# ET4207_DEBUG.net
KiCad netlist of a schematic drawn in Altium Designer
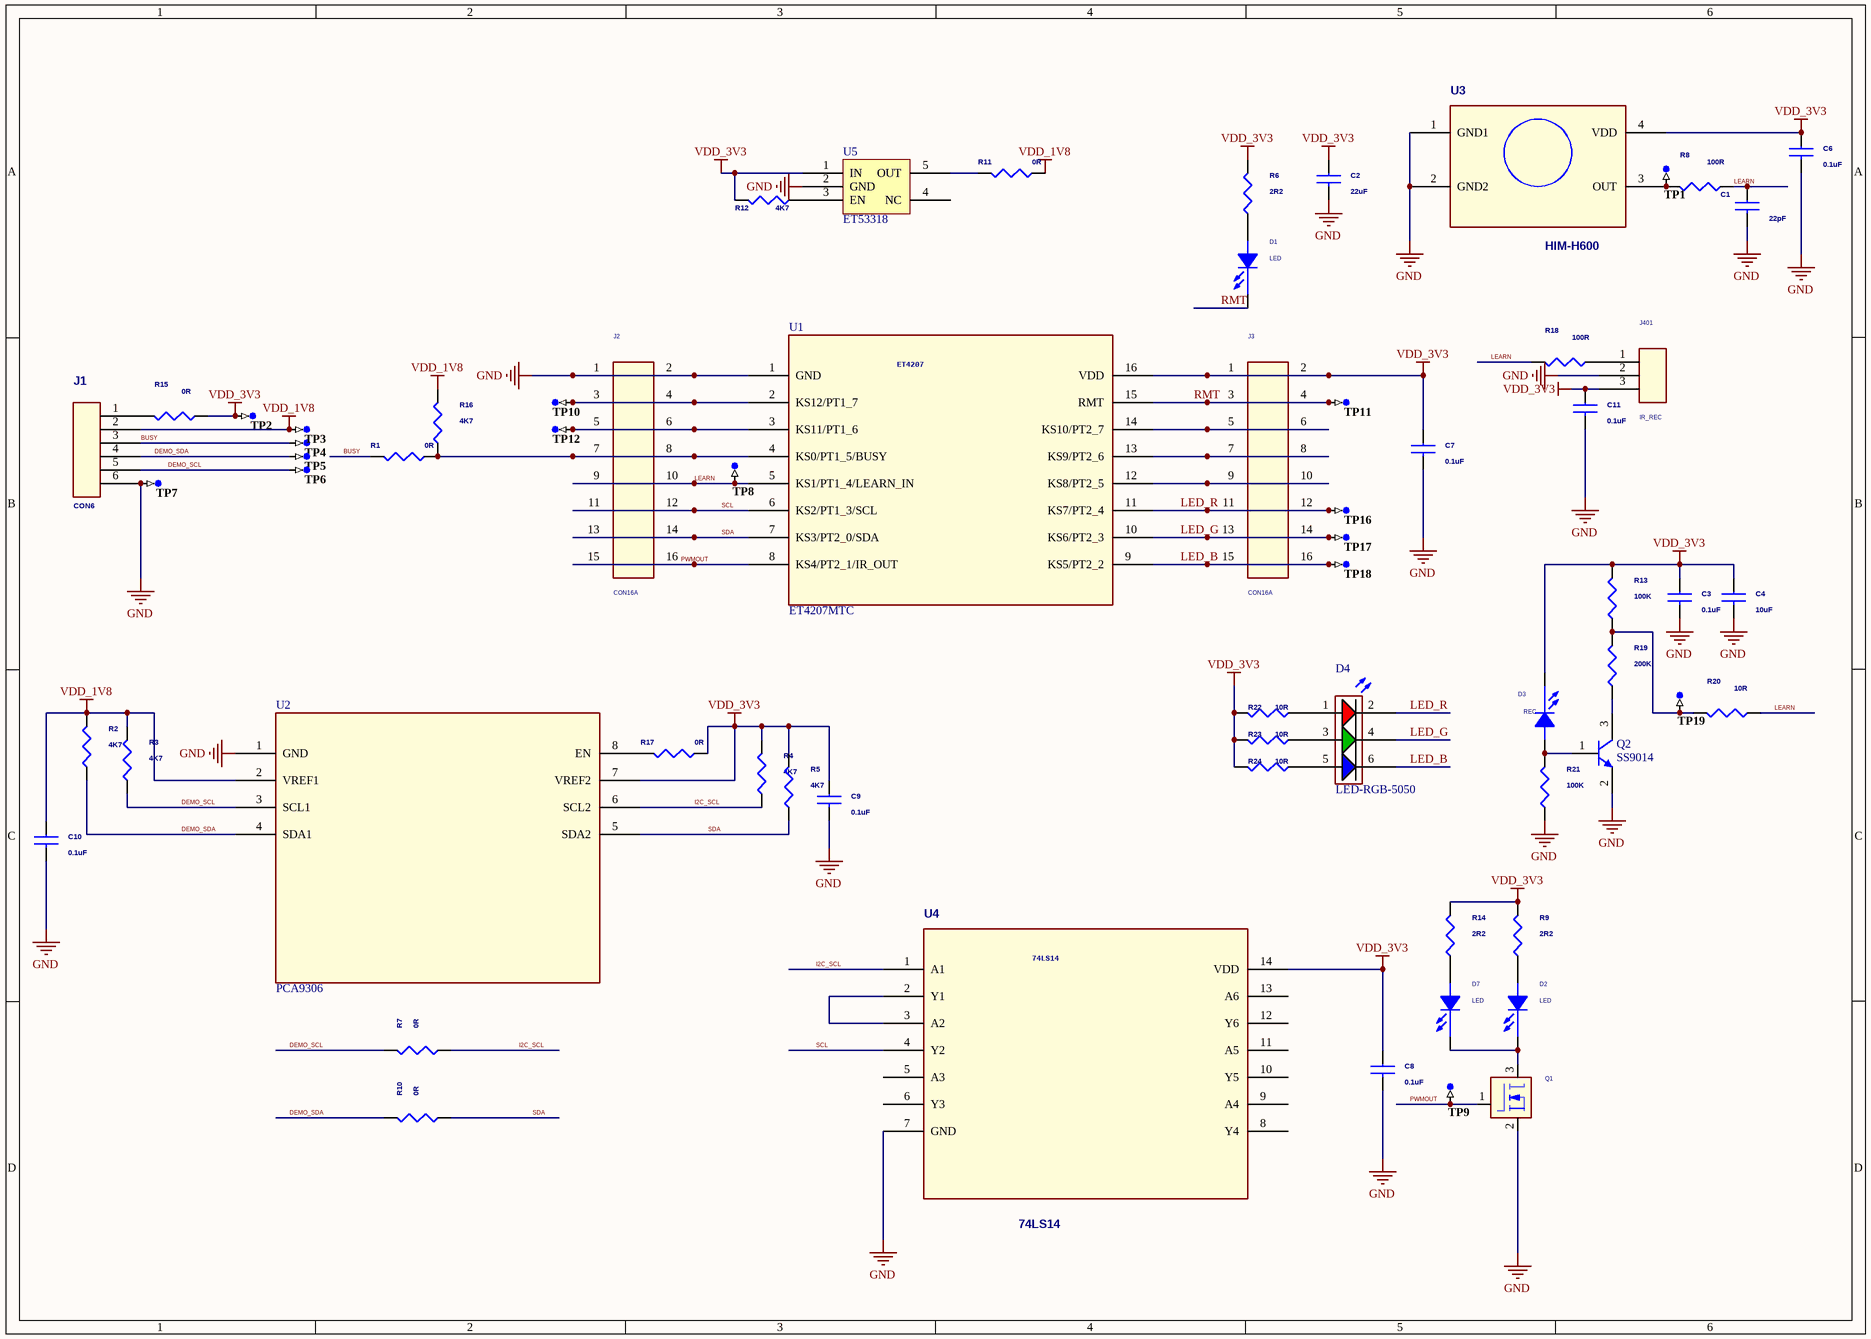
[diagram p0: ET4207_DEBUG.SchDoc]

(export (version "E")
  (design (tool "Eeschema 10.0.6"))
  (components
    (comp (ref "C1") (value "22pF") (footprint "0805C") (libsource (lib "*") (part "CAPACITOR NON-POL")))
    (comp (ref "C2") (value "22uF") (footprint "0805C") (libsource (lib "*") (part "CAPACITOR NON-POL")))
    (comp (ref "C3") (value "0.1uF") (footprint "0805C") (libsource (lib "*") (part "CAPACITOR NON-POL")))
    (comp (ref "C4") (value "10uF") (footprint "0805C") (libsource (lib "*") (part "CAPACITOR NON-POL")))
    (comp (ref "C6") (value "0.1uF") (footprint "0805C") (libsource (lib "*") (part "CAPACITOR NON-POL")))
    (comp (ref "C7") (value "0.1uF") (footprint "0805C") (libsource (lib "*") (part "CAPACITOR NON-POL")))
    (comp (ref "C8") (value "0.1uF") (footprint "0805C") (libsource (lib "*") (part "CAPACITOR NON-POL")))
    (comp (ref "C9") (value "0.1uF") (footprint "0805C") (libsource (lib "*") (part "CAPACITOR NON-POL")))
    (comp (ref "C10") (value "0.1uF") (footprint "0805C") (libsource (lib "*") (part "CAPACITOR NON-POL")))
    (comp (ref "C11") (value "0.1uF") (footprint "0805C") (libsource (lib "*") (part "CAPACITOR NON-POL")))
    (comp (ref "D1") (value "LED") (footprint "LED_A2") (libsource (lib "*") (part "LED_3")))
    (comp (ref "D2") (value "LED") (footprint "LED-0805") (libsource (lib "*") (part "LED_3")))
    (comp (ref "D3") (value "REC") (footprint "LED_A2") (libsource (lib "*") (part "LED_3")))
    (comp (ref "D4")
      (value "LED-RGB-5050")
      (footprint "LED-5050")
      (description "三基色LED")
      (fields (field (name "PUBLISHER") "Altium Limited"))
      (libsource (lib "sommer") (part "LED-RGB-5050"))
    )
    (comp (ref "D7") (value "LED") (footprint "LED_A2") (libsource (lib "*") (part "LED_3")))
    (comp (ref "J1") (value "CON6") (footprint "HDR1X6") (libsource (lib "*") (part "CON6")))
    (comp (ref "J2") (value "CON16A") (footprint "DIP16-2.54") (libsource (lib "*") (part "CON16A_0")))
    (comp (ref "J3") (value "CON16A") (footprint "DIP16-2.54") (libsource (lib "*") (part "CON16A_0")))
    (comp (ref "J401") (value "IR_REC") (footprint "IR") (libsource (lib "*") (part "CON3_0")))
    (comp (ref "Q1")
      (value "AO3400")
      (footprint "SOT-23")
      (description "MOSFET N-CH 50V 200MA SOT-23")
      (fields
        (field (name "TI_PART_NO") "TI-MOS-BSS138LT3G")
        (field (name "DISTRIBUTOR_PART_NUMBER") "BSS138LT3GOSCT-ND")
      )
      (libsource (lib "*") (part "MOSFET_I_EN_GSD"))
    )
    (comp (ref "Q2")
      (value "SS9014")
      (footprint "SOT23-3")
      (description "NPN贴片三极管")
      (fields (field (name "PUBLISHER") "Altium Limited"))
      (libsource (lib "sommer") (part "SS9014"))
    )
    (comp (ref "R1") (value "0R") (footprint "0805R") (libsource (lib "*") (part "RESISTOR")))
    (comp (ref "R2") (value "4K7") (footprint "0805R") (libsource (lib "*") (part "RESISTOR")))
    (comp (ref "R3") (value "4K7") (footprint "0805R") (libsource (lib "*") (part "RESISTOR")))
    (comp (ref "R4") (value "4K7") (footprint "0805R") (libsource (lib "*") (part "RESISTOR")))
    (comp (ref "R5") (value "4K7") (footprint "0805R") (libsource (lib "*") (part "RESISTOR")))
    (comp (ref "R6") (value "2R2") (footprint "0805R") (libsource (lib "*") (part "RESISTOR")))
    (comp (ref "R7") (value "0R") (footprint "0805R") (libsource (lib "*") (part "RESISTOR")))
    (comp (ref "R8") (value "100R") (footprint "0805R") (libsource (lib "*") (part "RESISTOR")))
    (comp (ref "R9") (value "2R2") (footprint "0805R") (libsource (lib "*") (part "RESISTOR")))
    (comp (ref "R10") (value "0R") (footprint "0805R") (libsource (lib "*") (part "RESISTOR")))
    (comp (ref "R11") (value "0R") (footprint "0805R") (libsource (lib "*") (part "RESISTOR")))
    (comp (ref "R12") (value "4K7") (footprint "0805R") (libsource (lib "*") (part "RESISTOR")))
    (comp (ref "R13") (value "100K") (footprint "0805R") (libsource (lib "*") (part "RESISTOR")))
    (comp (ref "R14") (value "2R2") (footprint "0805R") (libsource (lib "*") (part "RESISTOR")))
    (comp (ref "R15") (value "0R") (footprint "0805R") (libsource (lib "*") (part "RESISTOR")))
    (comp (ref "R16") (value "4K7") (footprint "0805R") (libsource (lib "*") (part "RESISTOR")))
    (comp (ref "R17") (value "0R") (footprint "0805R") (libsource (lib "*") (part "RESISTOR")))
    (comp (ref "R18") (value "100R") (footprint "0805R") (libsource (lib "*") (part "RESISTOR")))
    (comp (ref "R19") (value "200K") (footprint "0805R") (libsource (lib "*") (part "RESISTOR")))
    (comp (ref "R20") (value "10R") (footprint "0805R") (libsource (lib "*") (part "RESISTOR")))
    (comp (ref "R21") (value "100K") (footprint "0805R") (libsource (lib "*") (part "RESISTOR")))
    (comp (ref "R22") (value "10R") (footprint "0805R") (libsource (lib "*") (part "RESISTOR")))
    (comp (ref "R23") (value "10R") (footprint "0805R") (libsource (lib "*") (part "RESISTOR")))
    (comp (ref "R24") (value "10R") (footprint "0805R") (libsource (lib "*") (part "RESISTOR")))
    (comp (ref "TP1")
      (value "PULSE")
      (footprint "TP-SM-C-100")
      (description "Test Point, Surface Mount, Circular, Pad Diameter 1 mm")
      (libsource (lib "sommer") (part "TP-SM"))
    )
    (comp (ref "TP2")
      (value "3V3")
      (footprint "TP-SM-C-100")
      (description "Test Point, Surface Mount, Circular, Pad Diameter 1 mm")
      (libsource (lib "sommer") (part "TP-SM"))
    )
    (comp (ref "TP3")
      (value "1V8")
      (footprint "TP-SM-C-100")
      (description "Test Point, Surface Mount, Circular, Pad Diameter 1 mm")
      (libsource (lib "sommer") (part "TP-SM"))
    )
    (comp (ref "TP4")
      (value "BUSY")
      (footprint "TP-SM-C-100")
      (description "Test Point, Surface Mount, Circular, Pad Diameter 1 mm")
      (libsource (lib "sommer") (part "TP-SM"))
    )
    (comp (ref "TP5")
      (value "SDA")
      (footprint "TP-SM-C-100")
      (description "Test Point, Surface Mount, Circular, Pad Diameter 1 mm")
      (libsource (lib "sommer") (part "TP-SM"))
    )
    (comp (ref "TP6")
      (value "SCL")
      (footprint "TP-SM-C-100")
      (description "Test Point, Surface Mount, Circular, Pad Diameter 1 mm")
      (libsource (lib "sommer") (part "TP-SM"))
    )
    (comp (ref "TP7")
      (value "GND")
      (footprint "TP-SM-C-100")
      (description "Test Point, Surface Mount, Circular, Pad Diameter 1 mm")
      (libsource (lib "sommer") (part "TP-SM"))
    )
    (comp (ref "TP8")
      (value "LEARN")
      (footprint "TP-SM-C-100")
      (description "Test Point, Surface Mount, Circular, Pad Diameter 1 mm")
      (libsource (lib "sommer") (part "TP-SM"))
    )
    (comp (ref "TP9")
      (value "IROUT")
      (footprint "TP-SM-C-100")
      (description "Test Point, Surface Mount, Circular, Pad Diameter 1 mm")
      (libsource (lib "sommer") (part "TP-SM"))
    )
    (comp (ref "TP10")
      (value "PT17")
      (footprint "TP-SM-C-100")
      (description "Test Point, Surface Mount, Circular, Pad Diameter 1 mm")
      (libsource (lib "sommer") (part "TP-SM"))
    )
    (comp (ref "TP11")
      (value "SCL")
      (footprint "TP-SM-C-100")
      (description "Test Point, Surface Mount, Circular, Pad Diameter 1 mm")
      (libsource (lib "sommer") (part "TP-SM"))
    )
    (comp (ref "TP12")
      (value "PT16")
      (footprint "TP-SM-C-100")
      (description "Test Point, Surface Mount, Circular, Pad Diameter 1 mm")
      (libsource (lib "sommer") (part "TP-SM"))
    )
    (comp (ref "TP16")
      (value "PT24")
      (footprint "TP-SM-C-100")
      (description "Test Point, Surface Mount, Circular, Pad Diameter 1 mm")
      (libsource (lib "sommer") (part "TP-SM"))
    )
    (comp (ref "TP17")
      (value "PT23")
      (footprint "TP-SM-C-100")
      (description "Test Point, Surface Mount, Circular, Pad Diameter 1 mm")
      (libsource (lib "sommer") (part "TP-SM"))
    )
    (comp (ref "TP18")
      (value "PT22")
      (footprint "TP-SM-C-100")
      (description "Test Point, Surface Mount, Circular, Pad Diameter 1 mm")
      (libsource (lib "sommer") (part "TP-SM"))
    )
    (comp (ref "TP19")
      (value "DIODE_V")
      (footprint "TP-SM-C-100")
      (description "Test Point, Surface Mount, Circular, Pad Diameter 1 mm")
      (libsource (lib "sommer") (part "TP-SM"))
    )
    (comp (ref "U1")
      (value "ET4207MTC")
      (footprint "sommer:soic-16")
      (libsource (lib "ET4207_DEBUG_Library") (part "ET4207MTC"))
    )
    (comp (ref "U2")
      (value "PCA9306")
      (footprint "DCT-G8")
      (libsource (lib "ET4207_DEBUG_Library") (part "PCA9306"))
    )
    (comp (ref "U3") (value "HIM-H600") (footprint "HIM-H600") (libsource (lib "*") (part "LPC111x_7")))
    (comp (ref "U4")
      (value "74LS14")
      (footprint "sommer:SOIC-14")
      (libsource (lib "*") (part "STM32F103C8_1"))
    )
    (comp (ref "U5") (value "ET53318") (footprint "SOT23-5") (libsource (lib "sommer") (part "ET53333")))
  )
  (nets
    (net (code "1") (name "/BUSY") (class "Default")
      (node (ref "J1") (pin "3") (pinfunction "3_3") (pintype "passive"))
      (node (ref "R1") (pin "2") (pinfunction "2_2") (pintype "passive"))
      (node (ref "TP4") (pin "1") (pinfunction "1_1") (pintype "input"))
    )
    (net (code "2") (name "/DEMO_SCL") (class "Default")
      (node (ref "J1") (pin "5") (pinfunction "5_5") (pintype "passive"))
      (node (ref "R3") (pin "1") (pinfunction "1_1") (pintype "passive"))
      (node (ref "R7") (pin "2") (pinfunction "2_2") (pintype "passive"))
      (node (ref "TP6") (pin "1") (pinfunction "1_1") (pintype "input"))
      (node (ref "U2") (pin "3") (pinfunction "SCL1_3") (pintype "passive"))
    )
    (net (code "3") (name "/DEMO_SDA") (class "Default")
      (node (ref "J1") (pin "4") (pinfunction "4_4") (pintype "passive"))
      (node (ref "R10") (pin "2") (pinfunction "2_2") (pintype "passive"))
      (node (ref "R2") (pin "1") (pinfunction "1_1") (pintype "passive"))
      (node (ref "TP5") (pin "1") (pinfunction "1_1") (pintype "input"))
      (node (ref "U2") (pin "4") (pinfunction "SDA1_4") (pintype "passive"))
    )
    (net (code "4") (name "/I2C_SCL") (class "Default")
      (node (ref "R4") (pin "1") (pinfunction "1_1") (pintype "passive"))
      (node (ref "R7") (pin "1") (pinfunction "1_1") (pintype "passive"))
      (node (ref "U2") (pin "6") (pinfunction "SCL2_6") (pintype "passive"))
      (node (ref "U4") (pin "1") (pinfunction "A1_1") (pintype "passive"))
    )
    (net (code "5") (name "/LEARN") (class "Default")
      (node (ref "C1") (pin "1") (pinfunction "1_1") (pintype "passive"))
      (node (ref "J2") (pin "10") (pinfunction "10_10") (pintype "passive"))
      (node (ref "J2") (pin "9") (pinfunction "9_9") (pintype "passive"))
      (node (ref "R18") (pin "2") (pinfunction "2_2") (pintype "passive"))
      (node (ref "R20") (pin "1") (pinfunction "1_1") (pintype "passive"))
      (node (ref "R8") (pin "1") (pinfunction "1_1") (pintype "passive"))
      (node (ref "TP8") (pin "1") (pinfunction "1_1") (pintype "input"))
      (node (ref "U1") (pin "5") (pinfunction "KS1/PT1_4/LEARN_IN_5") (pintype "passive"))
    )
    (net (code "6") (name "/LED_B") (class "Default")
      (node (ref "D4") (pin "6") (pinfunction "B_6") (pintype "passive"))
      (node (ref "J3") (pin "15") (pinfunction "15_15") (pintype "passive"))
      (node (ref "J3") (pin "16") (pinfunction "16_16") (pintype "passive"))
      (node (ref "TP18") (pin "1") (pinfunction "1_1") (pintype "input"))
      (node (ref "U1") (pin "9") (pinfunction "KS5/PT2_2_9") (pintype "passive"))
    )
    (net (code "7") (name "/LED_G") (class "Default")
      (node (ref "D4") (pin "4") (pinfunction "G_4") (pintype "passive"))
      (node (ref "J3") (pin "13") (pinfunction "13_13") (pintype "passive"))
      (node (ref "J3") (pin "14") (pinfunction "14_14") (pintype "passive"))
      (node (ref "TP17") (pin "1") (pinfunction "1_1") (pintype "input"))
      (node (ref "U1") (pin "10") (pinfunction "KS6/PT2_3_10") (pintype "passive"))
    )
    (net (code "8") (name "/LED_R") (class "Default")
      (node (ref "D4") (pin "2") (pinfunction "R_2") (pintype "passive"))
      (node (ref "J3") (pin "11") (pinfunction "11_11") (pintype "passive"))
      (node (ref "J3") (pin "12") (pinfunction "12_12") (pintype "passive"))
      (node (ref "TP16") (pin "1") (pinfunction "1_1") (pintype "input"))
      (node (ref "U1") (pin "11") (pinfunction "KS7/PT2_4_11") (pintype "passive"))
    )
    (net (code "9") (name "/PWMOUT") (class "Default")
      (node (ref "J2") (pin "15") (pinfunction "15_15") (pintype "passive"))
      (node (ref "J2") (pin "16") (pinfunction "16_16") (pintype "passive"))
      (node (ref "Q1") (pin "1") (pinfunction "G_1") (pintype "passive"))
      (node (ref "TP9") (pin "1") (pinfunction "1_1") (pintype "input"))
      (node (ref "U1") (pin "8") (pinfunction "KS4/PT2_1/IR_OUT_8") (pintype "passive"))
    )
    (net (code "10") (name "/RMT") (class "Default")
      (node (ref "D1") (pin "2") (pinfunction "CATHODE_2") (pintype "passive"))
      (node (ref "J3") (pin "3") (pinfunction "3_3") (pintype "passive"))
      (node (ref "J3") (pin "4") (pinfunction "4_4") (pintype "passive"))
      (node (ref "TP11") (pin "1") (pinfunction "1_1") (pintype "input"))
      (node (ref "U1") (pin "15") (pinfunction "RMT_15") (pintype "passive"))
    )
    (net (code "11") (name "/SCL") (class "Default")
      (node (ref "J2") (pin "11") (pinfunction "11_11") (pintype "passive"))
      (node (ref "J2") (pin "12") (pinfunction "12_12") (pintype "passive"))
      (node (ref "U1") (pin "6") (pinfunction "KS2/PT1_3/SCL_6") (pintype "passive"))
      (node (ref "U4") (pin "4") (pinfunction "Y2_4") (pintype "passive"))
    )
    (net (code "12") (name "/SDA") (class "Default")
      (node (ref "J2") (pin "13") (pinfunction "13_13") (pintype "passive"))
      (node (ref "J2") (pin "14") (pinfunction "14_14") (pintype "passive"))
      (node (ref "R10") (pin "1") (pinfunction "1_1") (pintype "passive"))
      (node (ref "R5") (pin "1") (pinfunction "1_1") (pintype "passive"))
      (node (ref "U1") (pin "7") (pinfunction "KS3/PT2_0/SDA_7") (pintype "passive"))
      (node (ref "U2") (pin "5") (pinfunction "SDA2_5") (pintype "passive"))
    )
    (net (code "13") (name "GND") (class "Default")
      (node (ref "C1") (pin "2") (pinfunction "2_2") (pintype "passive"))
      (node (ref "C10") (pin "2") (pinfunction "2_2") (pintype "passive"))
      (node (ref "C11") (pin "2") (pinfunction "2_2") (pintype "passive"))
      (node (ref "C2") (pin "2") (pinfunction "2_2") (pintype "passive"))
      (node (ref "C3") (pin "2") (pinfunction "2_2") (pintype "passive"))
      (node (ref "C4") (pin "2") (pinfunction "2_2") (pintype "passive"))
      (node (ref "C6") (pin "2") (pinfunction "2_2") (pintype "passive"))
      (node (ref "C7") (pin "2") (pinfunction "2_2") (pintype "passive"))
      (node (ref "C8") (pin "2") (pinfunction "2_2") (pintype "passive"))
      (node (ref "C9") (pin "2") (pinfunction "2_2") (pintype "passive"))
      (node (ref "J1") (pin "6") (pinfunction "6_6") (pintype "passive"))
      (node (ref "J2") (pin "1") (pinfunction "1_1") (pintype "passive"))
      (node (ref "J2") (pin "2") (pinfunction "2_2") (pintype "passive"))
      (node (ref "J401") (pin "2") (pinfunction "GND_2") (pintype "passive"))
      (node (ref "Q1") (pin "2") (pinfunction "S_2") (pintype "passive"))
      (node (ref "Q2") (pin "2") (pinfunction "E_2") (pintype "passive"))
      (node (ref "R21") (pin "1") (pinfunction "1_1") (pintype "passive"))
      (node (ref "TP7") (pin "1") (pinfunction "1_1") (pintype "input"))
      (node (ref "U1") (pin "1") (pinfunction "GND_1") (pintype "passive"))
      (node (ref "U2") (pin "1") (pinfunction "GND_1") (pintype "passive"))
      (node (ref "U3") (pin "1") (pinfunction "GND1_1") (pintype "passive"))
      (node (ref "U3") (pin "2") (pinfunction "GND2_2") (pintype "passive"))
      (node (ref "U4") (pin "7") (pinfunction "GND_7") (pintype "passive"))
      (node (ref "U5") (pin "2") (pinfunction "GND_2") (pintype "passive"))
    )
    (net (code "14") (name "Net-(D1-ANODE)") (class "Default")
      (node (ref "D1") (pin "1") (pinfunction "ANODE_1") (pintype "passive"))
      (node (ref "R6") (pin "1") (pinfunction "1_1") (pintype "passive"))
    )
    (net (code "15") (name "Net-(D2-ANODE)") (class "Default")
      (node (ref "D2") (pin "1") (pinfunction "ANODE_1") (pintype "passive"))
      (node (ref "R9") (pin "1") (pinfunction "1_1") (pintype "passive"))
    )
    (net (code "16") (name "Net-(D2-CATHODE)") (class "Default")
      (node (ref "D2") (pin "2") (pinfunction "CATHODE_2") (pintype "passive"))
      (node (ref "D7") (pin "2") (pinfunction "CATHODE_2") (pintype "passive"))
      (node (ref "Q1") (pin "3") (pinfunction "D_3") (pintype "passive"))
    )
    (net (code "17") (name "Net-(D3-ANODE)") (class "Default")
      (node (ref "D3") (pin "1") (pinfunction "ANODE_1") (pintype "passive"))
      (node (ref "Q2") (pin "1") (pinfunction "B_1") (pintype "passive"))
      (node (ref "R21") (pin "2") (pinfunction "2_2") (pintype "passive"))
    )
    (net (code "18") (name "Net-(D4-A)") (class "Default")
      (node (ref "D4") (pin "3") (pinfunction "A_3") (pintype "passive"))
      (node (ref "R23") (pin "1") (pinfunction "1_1") (pintype "passive"))
    )
    (net (code "19") (name "Net-(D4-R-Pad1)") (class "Default")
      (node (ref "D4") (pin "1") (pinfunction "R_1") (pintype "passive"))
      (node (ref "R22") (pin "1") (pinfunction "1_1") (pintype "passive"))
    )
    (net (code "20") (name "Net-(D4-R-Pad5)") (class "Default")
      (node (ref "D4") (pin "5") (pinfunction "R_5") (pintype "passive"))
      (node (ref "R24") (pin "1") (pinfunction "1_1") (pintype "passive"))
    )
    (net (code "21") (name "Net-(D7-ANODE)") (class "Default")
      (node (ref "D7") (pin "1") (pinfunction "ANODE_1") (pintype "passive"))
      (node (ref "R14") (pin "1") (pinfunction "1_1") (pintype "passive"))
    )
    (net (code "22") (name "Net-(J1-Pad1)") (class "Default")
      (node (ref "J1") (pin "1") (pinfunction "1_1") (pintype "passive"))
      (node (ref "R15") (pin "2") (pinfunction "2_2") (pintype "passive"))
    )
    (net (code "23") (name "Net-(J401-IROUT)") (class "Default")
      (node (ref "J401") (pin "1") (pinfunction "IROUT_1") (pintype "passive"))
      (node (ref "R18") (pin "1") (pinfunction "1_1") (pintype "passive"))
    )
    (net (code "24") (name "Net-(Q2-C)") (class "Default")
      (node (ref "Q2") (pin "3") (pinfunction "C_3") (pintype "passive"))
      (node (ref "R19") (pin "1") (pinfunction "1_1") (pintype "passive"))
    )
    (net (code "25") (name "Net-(R13-Pad1)") (class "Default")
      (node (ref "R13") (pin "1") (pinfunction "1_1") (pintype "passive"))
      (node (ref "R19") (pin "2") (pinfunction "2_2") (pintype "passive"))
      (node (ref "R20") (pin "2") (pinfunction "2_2") (pintype "passive"))
      (node (ref "TP19") (pin "1") (pinfunction "1_1") (pintype "input"))
    )
    (net (code "26") (name "Net-(U1-KS0{slash}PT1_5{slash}BUSY)") (class "Default")
      (node (ref "J2") (pin "7") (pinfunction "7_7") (pintype "passive"))
      (node (ref "J2") (pin "8") (pinfunction "8_8") (pintype "passive"))
      (node (ref "R1") (pin "1") (pinfunction "1_1") (pintype "passive"))
      (node (ref "R16") (pin "1") (pinfunction "1_1") (pintype "passive"))
      (node (ref "U1") (pin "4") (pinfunction "KS0/PT1_5/BUSY_4") (pintype "passive"))
    )
    (net (code "27") (name "Net-(U1-KS8{slash}PT2_5)") (class "Default")
      (node (ref "J3") (pin "10") (pinfunction "10_10") (pintype "passive"))
      (node (ref "J3") (pin "9") (pinfunction "9_9") (pintype "passive"))
      (node (ref "U1") (pin "12") (pinfunction "KS8/PT2_5_12") (pintype "passive"))
    )
    (net (code "28") (name "Net-(U1-KS9{slash}PT2_6)") (class "Default")
      (node (ref "J3") (pin "7") (pinfunction "7_7") (pintype "passive"))
      (node (ref "J3") (pin "8") (pinfunction "8_8") (pintype "passive"))
      (node (ref "U1") (pin "13") (pinfunction "KS9/PT2_6_13") (pintype "passive"))
    )
    (net (code "29") (name "Net-(U1-KS10{slash}PT2_7)") (class "Default")
      (node (ref "J3") (pin "5") (pinfunction "5_5") (pintype "passive"))
      (node (ref "J3") (pin "6") (pinfunction "6_6") (pintype "passive"))
      (node (ref "U1") (pin "14") (pinfunction "KS10/PT2_7_14") (pintype "passive"))
    )
    (net (code "30") (name "Net-(U1-KS11{slash}PT1_6)") (class "Default")
      (node (ref "J2") (pin "5") (pinfunction "5_5") (pintype "passive"))
      (node (ref "J2") (pin "6") (pinfunction "6_6") (pintype "passive"))
      (node (ref "TP12") (pin "1") (pinfunction "1_1") (pintype "input"))
      (node (ref "U1") (pin "3") (pinfunction "KS11/PT1_6_3") (pintype "passive"))
    )
    (net (code "31") (name "Net-(U1-KS12{slash}PT1_7)") (class "Default")
      (node (ref "J2") (pin "3") (pinfunction "3_3") (pintype "passive"))
      (node (ref "J2") (pin "4") (pinfunction "4_4") (pintype "passive"))
      (node (ref "TP10") (pin "1") (pinfunction "1_1") (pintype "input"))
      (node (ref "U1") (pin "2") (pinfunction "KS12/PT1_7_2") (pintype "passive"))
    )
    (net (code "32") (name "Net-(U2-EN)") (class "Default")
      (node (ref "R17") (pin "2") (pinfunction "2_2") (pintype "passive"))
      (node (ref "U2") (pin "8") (pinfunction "EN_8") (pintype "passive"))
    )
    (net (code "33") (name "Net-(U3-OUT)") (class "Default")
      (node (ref "R8") (pin "2") (pinfunction "2_2") (pintype "passive"))
      (node (ref "TP1") (pin "1") (pinfunction "1_1") (pintype "input"))
      (node (ref "U3") (pin "3") (pinfunction "OUT_3") (pintype "passive"))
    )
    (net (code "34") (name "Net-(U4-A2)") (class "Default")
      (node (ref "U4") (pin "2") (pinfunction "Y1_2") (pintype "passive"))
      (node (ref "U4") (pin "3") (pinfunction "A2_3") (pintype "passive"))
    )
    (net (code "35") (name "Net-(U5-EN)") (class "Default")
      (node (ref "R12") (pin "1") (pinfunction "1_1") (pintype "passive"))
      (node (ref "U5") (pin "3") (pinfunction "EN_3") (pintype "passive"))
    )
    (net (code "36") (name "Net-(U5-OUT)") (class "Default")
      (node (ref "R11") (pin "2") (pinfunction "2_2") (pintype "passive"))
      (node (ref "U5") (pin "5") (pinfunction "OUT_5") (pintype "passive"))
    )
    (net (code "37") (name "VDD_1V8") (class "Default")
      (node (ref "C10") (pin "1") (pinfunction "1_1") (pintype "passive"))
      (node (ref "J1") (pin "2") (pinfunction "2_2") (pintype "passive"))
      (node (ref "R11") (pin "1") (pinfunction "1_1") (pintype "passive"))
      (node (ref "R16") (pin "2") (pinfunction "2_2") (pintype "passive"))
      (node (ref "R2") (pin "2") (pinfunction "2_2") (pintype "passive"))
      (node (ref "R3") (pin "2") (pinfunction "2_2") (pintype "passive"))
      (node (ref "TP3") (pin "1") (pinfunction "1_1") (pintype "input"))
      (node (ref "U2") (pin "2") (pinfunction "VREF1_2") (pintype "passive"))
    )
    (net (code "38") (name "VDD_3V3") (class "Default")
      (node (ref "C11") (pin "1") (pinfunction "1_1") (pintype "passive"))
      (node (ref "C2") (pin "1") (pinfunction "1_1") (pintype "passive"))
      (node (ref "C3") (pin "1") (pinfunction "1_1") (pintype "passive"))
      (node (ref "C4") (pin "1") (pinfunction "1_1") (pintype "passive"))
      (node (ref "C6") (pin "1") (pinfunction "1_1") (pintype "passive"))
      (node (ref "C7") (pin "1") (pinfunction "1_1") (pintype "passive"))
      (node (ref "C8") (pin "1") (pinfunction "1_1") (pintype "passive"))
      (node (ref "C9") (pin "1") (pinfunction "1_1") (pintype "passive"))
      (node (ref "D3") (pin "2") (pinfunction "CATHODE_2") (pintype "passive"))
      (node (ref "J3") (pin "1") (pinfunction "1_1") (pintype "passive"))
      (node (ref "J3") (pin "2") (pinfunction "2_2") (pintype "passive"))
      (node (ref "J401") (pin "3") (pinfunction "VCC_3") (pintype "passive"))
      (node (ref "R12") (pin "2") (pinfunction "2_2") (pintype "passive"))
      (node (ref "R13") (pin "2") (pinfunction "2_2") (pintype "passive"))
      (node (ref "R14") (pin "2") (pinfunction "2_2") (pintype "passive"))
      (node (ref "R15") (pin "1") (pinfunction "1_1") (pintype "passive"))
      (node (ref "R17") (pin "1") (pinfunction "1_1") (pintype "passive"))
      (node (ref "R22") (pin "2") (pinfunction "2_2") (pintype "passive"))
      (node (ref "R23") (pin "2") (pinfunction "2_2") (pintype "passive"))
      (node (ref "R24") (pin "2") (pinfunction "2_2") (pintype "passive"))
      (node (ref "R4") (pin "2") (pinfunction "2_2") (pintype "passive"))
      (node (ref "R5") (pin "2") (pinfunction "2_2") (pintype "passive"))
      (node (ref "R6") (pin "2") (pinfunction "2_2") (pintype "passive"))
      (node (ref "R9") (pin "2") (pinfunction "2_2") (pintype "passive"))
      (node (ref "TP2") (pin "1") (pinfunction "1_1") (pintype "input"))
      (node (ref "U1") (pin "16") (pinfunction "VDD_16") (pintype "passive"))
      (node (ref "U2") (pin "7") (pinfunction "VREF2_7") (pintype "passive"))
      (node (ref "U3") (pin "4") (pinfunction "VDD_4") (pintype "passive"))
      (node (ref "U4") (pin "14") (pinfunction "VDD_14") (pintype "passive"))
      (node (ref "U5") (pin "1") (pinfunction "IN_1") (pintype "passive"))
    )
    (net (code "39") (name "unconnected-(U4-A3-Pad5)") (class "Default")
      (node (ref "U4") (pin "5") (pinfunction "A3_5") (pintype "passive"))
    )
    (net (code "40") (name "unconnected-(U4-A4-Pad9)") (class "Default")
      (node (ref "U4") (pin "9") (pinfunction "A4_9") (pintype "passive"))
    )
    (net (code "41") (name "unconnected-(U4-A5-Pad11)") (class "Default")
      (node (ref "U4") (pin "11") (pinfunction "A5_11") (pintype "passive"))
    )
    (net (code "42") (name "unconnected-(U4-A6-Pad13)") (class "Default")
      (node (ref "U4") (pin "13") (pinfunction "A6_13") (pintype "passive"))
    )
    (net (code "43") (name "unconnected-(U4-Y3-Pad6)") (class "Default")
      (node (ref "U4") (pin "6") (pinfunction "Y3_6") (pintype "passive"))
    )
    (net (code "44") (name "unconnected-(U4-Y4-Pad8)") (class "Default")
      (node (ref "U4") (pin "8") (pinfunction "Y4_8") (pintype "passive"))
    )
    (net (code "45") (name "unconnected-(U4-Y5-Pad10)") (class "Default")
      (node (ref "U4") (pin "10") (pinfunction "Y5_10") (pintype "passive"))
    )
    (net (code "46") (name "unconnected-(U4-Y6-Pad12)") (class "Default")
      (node (ref "U4") (pin "12") (pinfunction "Y6_12") (pintype "passive"))
    )
    (net (code "47") (name "unconnected-(U5-NC-Pad4)") (class "Default")
      (node (ref "U5") (pin "4") (pinfunction "NC_4") (pintype "passive"))
    )
  )
)
